# COMM.net
KiCad netlist of a schematic drawn in Altium Designer
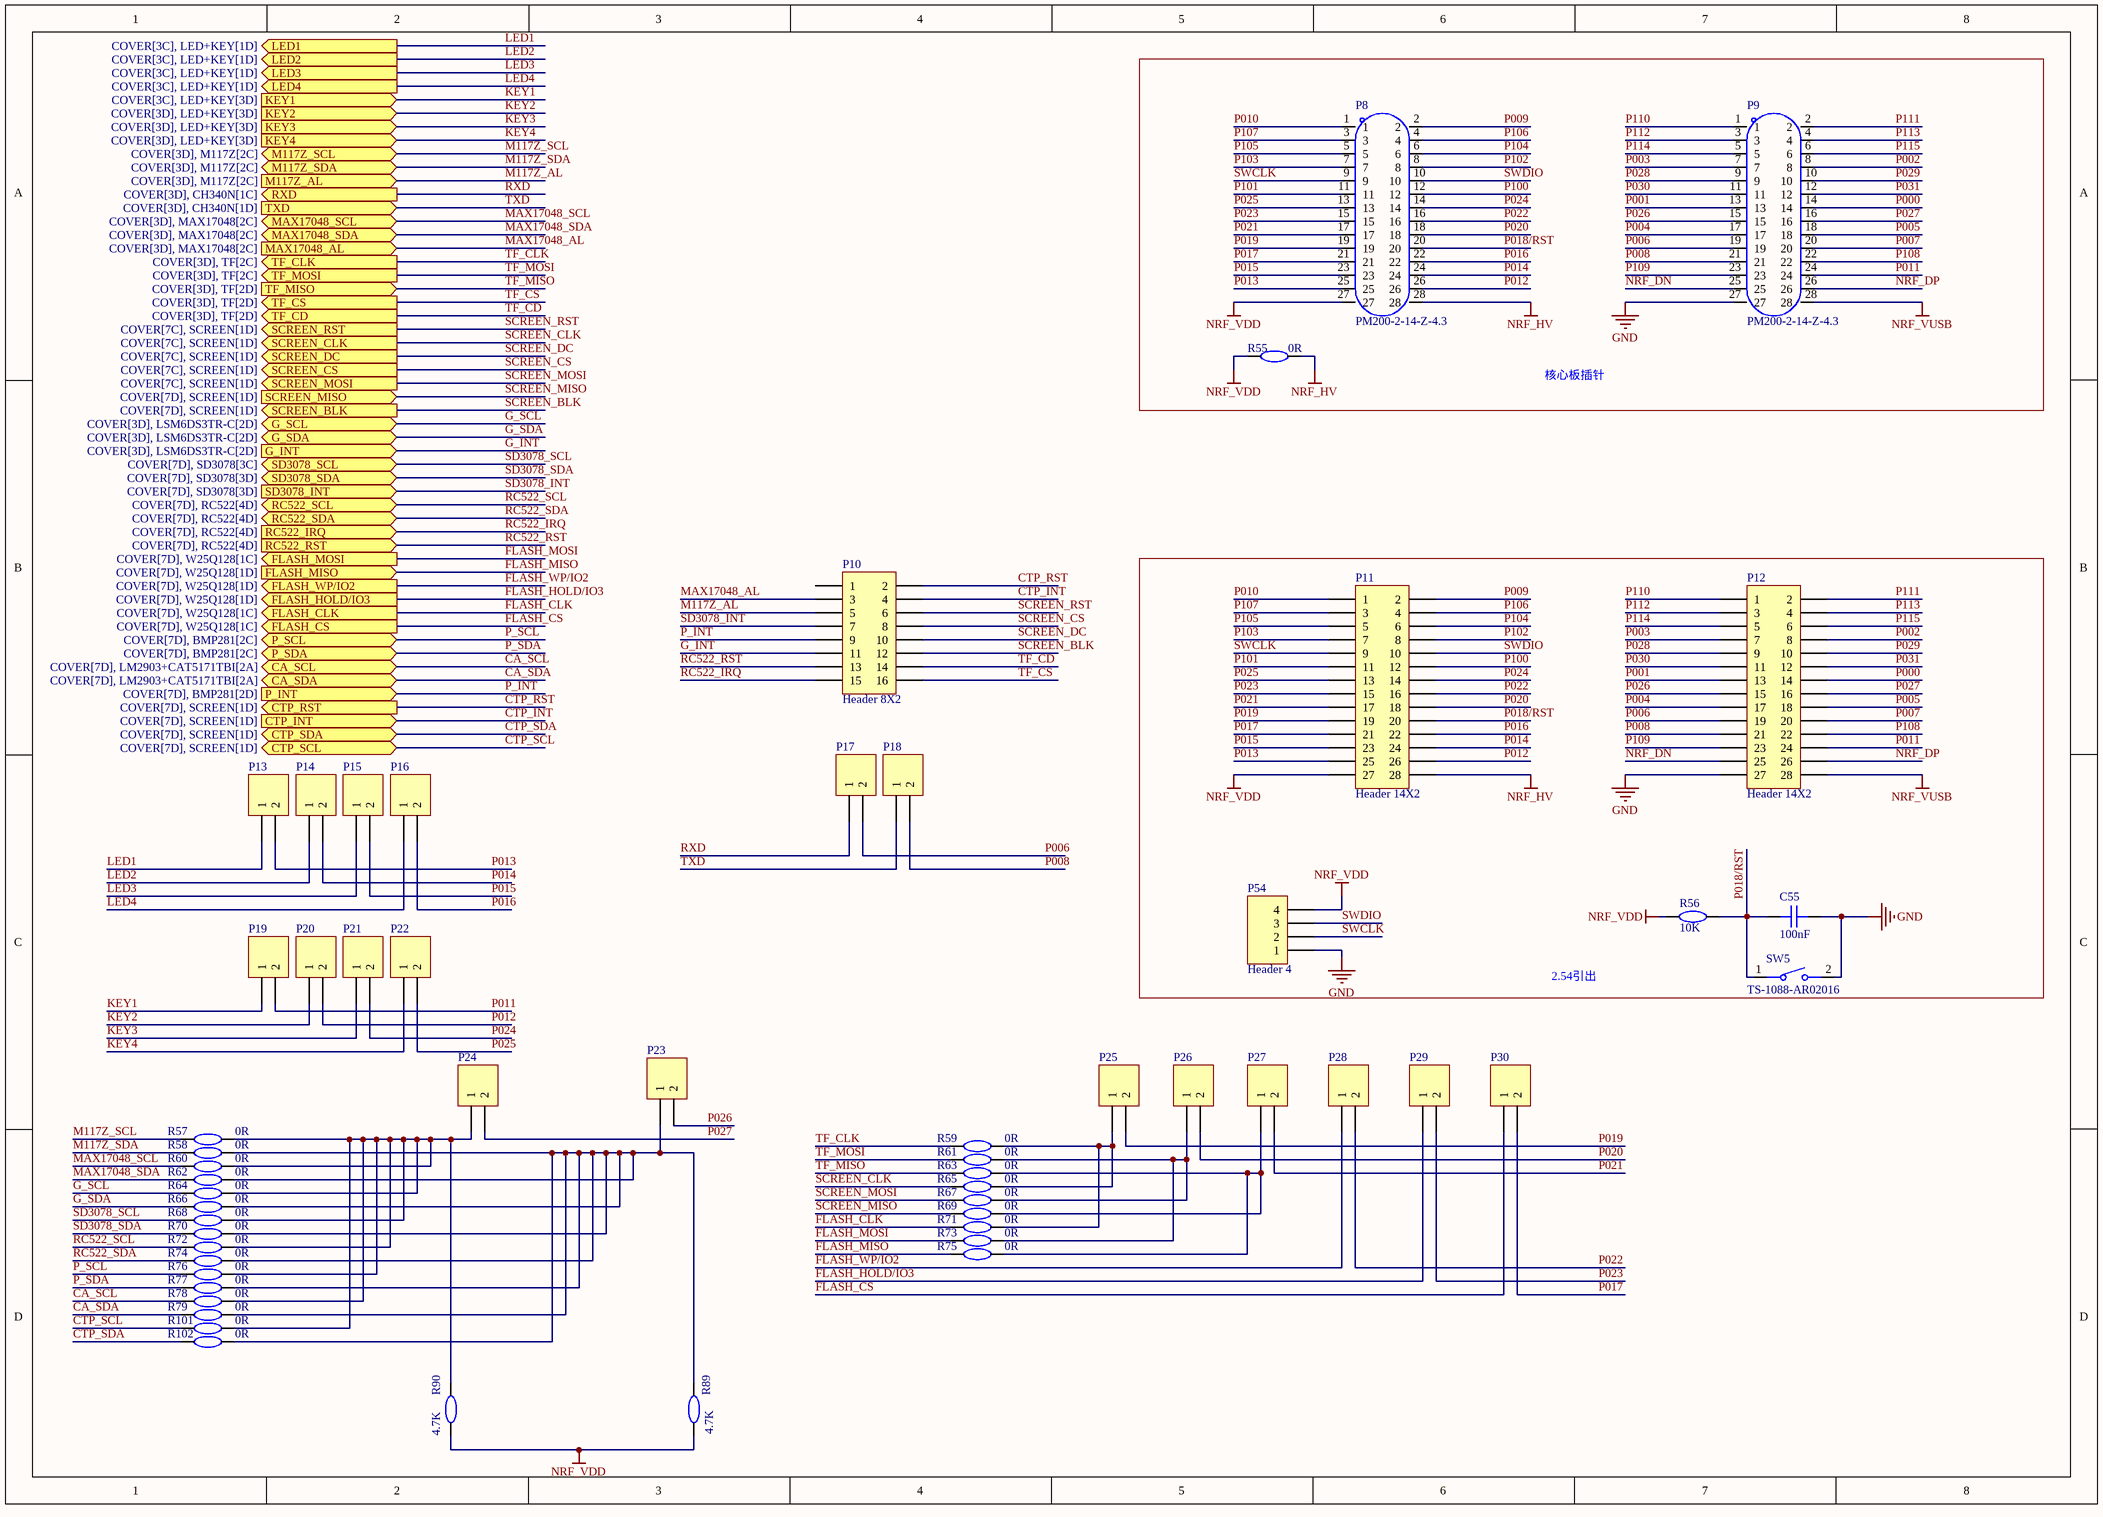
[diagram p0: COMM.SchDoc]

(export (version "E")
  (design (tool "Eeschema 10.0.6"))
  (components
    (comp (ref "C55")
      (value "100nF")
      (footprint "C0402")
      (fields (field (name "NAME") "100nF"))
      (libsource (lib "my_library") (part "CAP_0402"))
    )
    (comp (ref "P8")
      (value "PM200-2-14-Z-4.3")
      (footprint "HDR-TH_28P-P2.00-V-F-R2-C14-S2.00_MF200V-12-28-0590")
      (fields (field (name "MANUFACTURER") "HCTL(华灿天禄)") (field (name "NAME") "PM200-2-14-Z-4.3"))
      (libsource (lib "my_library") (part "PM200-2-14-Z-4.3_C3012178"))
    )
    (comp (ref "P9")
      (value "PM200-2-14-Z-4.3")
      (footprint "HDR-TH_28P-P2.00-V-F-R2-C14-S2.00_MF200V-12-28-0590")
      (fields (field (name "MANUFACTURER") "HCTL(华灿天禄)") (field (name "NAME") "PM200-2-14-Z-4.3"))
      (libsource (lib "my_library") (part "PM200-2-14-Z-4.3_C3012178"))
    )
    (comp (ref "P10")
      (value "Header 8X2")
      (footprint "HDR2X8")
      (description "Header, 8-Pin, Dual row")
      (fields (field (name "PUBLISHER") "Altium Limited"))
      (libsource (lib "Miscellaneous Connectors") (part "Header 8X2"))
    )
    (comp (ref "P11")
      (value "Header 14X2")
      (footprint "HDR2X14")
      (description "Header, 14-Pin, Dual row")
      (fields (field (name "PUBLISHER") "Altium Limited"))
      (libsource (lib "Miscellaneous Connectors") (part "Header 14X2"))
    )
    (comp (ref "P12")
      (value "Header 14X2")
      (footprint "HDR2X14")
      (description "Header, 14-Pin, Dual row")
      (fields (field (name "PUBLISHER") "Altium Limited"))
      (libsource (lib "Miscellaneous Connectors") (part "Header 14X2"))
    )
    (comp (ref "P13")
      (value "Header 2")
      (footprint "HDR1X2")
      (description "Header, 2-Pin")
      (fields (field (name "PUBLISHER") "Altium Limited"))
      (libsource (lib "Miscellaneous Connectors") (part "Header 2"))
    )
    (comp (ref "P14")
      (value "Header 2")
      (footprint "HDR1X2")
      (description "Header, 2-Pin")
      (fields (field (name "PUBLISHER") "Altium Limited"))
      (libsource (lib "Miscellaneous Connectors") (part "Header 2"))
    )
    (comp (ref "P15")
      (value "Header 2")
      (footprint "HDR1X2")
      (description "Header, 2-Pin")
      (fields (field (name "PUBLISHER") "Altium Limited"))
      (libsource (lib "Miscellaneous Connectors") (part "Header 2"))
    )
    (comp (ref "P16")
      (value "Header 2")
      (footprint "HDR1X2")
      (description "Header, 2-Pin")
      (fields (field (name "PUBLISHER") "Altium Limited"))
      (libsource (lib "Miscellaneous Connectors") (part "Header 2"))
    )
    (comp (ref "P17")
      (value "Header 2")
      (footprint "HDR1X2")
      (description "Header, 2-Pin")
      (fields (field (name "PUBLISHER") "Altium Limited"))
      (libsource (lib "Miscellaneous Connectors") (part "Header 2"))
    )
    (comp (ref "P18")
      (value "Header 2")
      (footprint "HDR1X2")
      (description "Header, 2-Pin")
      (fields (field (name "PUBLISHER") "Altium Limited"))
      (libsource (lib "Miscellaneous Connectors") (part "Header 2"))
    )
    (comp (ref "P19")
      (value "Header 2")
      (footprint "HDR1X2")
      (description "Header, 2-Pin")
      (fields (field (name "PUBLISHER") "Altium Limited"))
      (libsource (lib "Miscellaneous Connectors") (part "Header 2"))
    )
    (comp (ref "P20")
      (value "Header 2")
      (footprint "HDR1X2")
      (description "Header, 2-Pin")
      (fields (field (name "PUBLISHER") "Altium Limited"))
      (libsource (lib "Miscellaneous Connectors") (part "Header 2"))
    )
    (comp (ref "P21")
      (value "Header 2")
      (footprint "HDR1X2")
      (description "Header, 2-Pin")
      (fields (field (name "PUBLISHER") "Altium Limited"))
      (libsource (lib "Miscellaneous Connectors") (part "Header 2"))
    )
    (comp (ref "P22")
      (value "Header 2")
      (footprint "HDR1X2")
      (description "Header, 2-Pin")
      (fields (field (name "PUBLISHER") "Altium Limited"))
      (libsource (lib "Miscellaneous Connectors") (part "Header 2"))
    )
    (comp (ref "P23")
      (value "Header 2")
      (footprint "HDR1X2")
      (description "Header, 2-Pin")
      (fields (field (name "PUBLISHER") "Altium Limited"))
      (libsource (lib "Miscellaneous Connectors") (part "Header 2"))
    )
    (comp (ref "P24")
      (value "Header 2")
      (footprint "HDR1X2")
      (description "Header, 2-Pin")
      (fields (field (name "PUBLISHER") "Altium Limited"))
      (libsource (lib "Miscellaneous Connectors") (part "Header 2"))
    )
    (comp (ref "P25")
      (value "Header 2")
      (footprint "HDR1X2")
      (description "Header, 2-Pin")
      (fields (field (name "PUBLISHER") "Altium Limited"))
      (libsource (lib "Miscellaneous Connectors") (part "Header 2"))
    )
    (comp (ref "P26")
      (value "Header 2")
      (footprint "HDR1X2")
      (description "Header, 2-Pin")
      (fields (field (name "PUBLISHER") "Altium Limited"))
      (libsource (lib "Miscellaneous Connectors") (part "Header 2"))
    )
    (comp (ref "P27")
      (value "Header 2")
      (footprint "HDR1X2")
      (description "Header, 2-Pin")
      (fields (field (name "PUBLISHER") "Altium Limited"))
      (libsource (lib "Miscellaneous Connectors") (part "Header 2"))
    )
    (comp (ref "P28")
      (value "Header 2")
      (footprint "HDR1X2")
      (description "Header, 2-Pin")
      (fields (field (name "PUBLISHER") "Altium Limited"))
      (libsource (lib "Miscellaneous Connectors") (part "Header 2"))
    )
    (comp (ref "P29")
      (value "Header 2")
      (footprint "HDR1X2")
      (description "Header, 2-Pin")
      (fields (field (name "PUBLISHER") "Altium Limited"))
      (libsource (lib "Miscellaneous Connectors") (part "Header 2"))
    )
    (comp (ref "P30")
      (value "Header 2")
      (footprint "HDR1X2")
      (description "Header, 2-Pin")
      (fields (field (name "PUBLISHER") "Altium Limited"))
      (libsource (lib "Miscellaneous Connectors") (part "Header 2"))
    )
    (comp (ref "P54")
      (value "Header 4")
      (footprint "HDR1X4")
      (description "Header, 4-Pin")
      (fields (field (name "PUBLISHER") "Altium Limited"))
      (libsource (lib "Miscellaneous Connectors") (part "Header 4"))
    )
    (comp (ref "R55")
      (value "0R")
      (footprint "R0402")
      (fields (field (name "NAME") "0R"))
      (libsource (lib "my_library") (part "Res_0402"))
    )
    (comp (ref "R56")
      (value "10K")
      (footprint "R0402")
      (fields (field (name "NAME") "10K"))
      (libsource (lib "my_library") (part "Res_0402"))
    )
    (comp (ref "R57")
      (value "0R")
      (footprint "R0402")
      (fields (field (name "NAME") "0R"))
      (libsource (lib "my_library") (part "Res_0402"))
    )
    (comp (ref "R58")
      (value "0R")
      (footprint "R0402")
      (fields (field (name "NAME") "0R"))
      (libsource (lib "my_library") (part "Res_0402"))
    )
    (comp (ref "R59")
      (value "0R")
      (footprint "R0402")
      (fields (field (name "NAME") "0R"))
      (libsource (lib "my_library") (part "Res_0402"))
    )
    (comp (ref "R60")
      (value "0R")
      (footprint "R0402")
      (fields (field (name "NAME") "0R"))
      (libsource (lib "my_library") (part "Res_0402"))
    )
    (comp (ref "R61")
      (value "0R")
      (footprint "R0402")
      (fields (field (name "NAME") "0R"))
      (libsource (lib "my_library") (part "Res_0402"))
    )
    (comp (ref "R62")
      (value "0R")
      (footprint "R0402")
      (fields (field (name "NAME") "0R"))
      (libsource (lib "my_library") (part "Res_0402"))
    )
    (comp (ref "R63")
      (value "0R")
      (footprint "R0402")
      (fields (field (name "NAME") "0R"))
      (libsource (lib "my_library") (part "Res_0402"))
    )
    (comp (ref "R64")
      (value "0R")
      (footprint "R0402")
      (fields (field (name "NAME") "0R"))
      (libsource (lib "my_library") (part "Res_0402"))
    )
    (comp (ref "R65")
      (value "0R")
      (footprint "R0402")
      (fields (field (name "NAME") "0R"))
      (libsource (lib "my_library") (part "Res_0402"))
    )
    (comp (ref "R66")
      (value "0R")
      (footprint "R0402")
      (fields (field (name "NAME") "0R"))
      (libsource (lib "my_library") (part "Res_0402"))
    )
    (comp (ref "R67")
      (value "0R")
      (footprint "R0402")
      (fields (field (name "NAME") "0R"))
      (libsource (lib "my_library") (part "Res_0402"))
    )
    (comp (ref "R68")
      (value "0R")
      (footprint "R0402")
      (fields (field (name "NAME") "0R"))
      (libsource (lib "my_library") (part "Res_0402"))
    )
    (comp (ref "R69")
      (value "0R")
      (footprint "R0402")
      (fields (field (name "NAME") "0R"))
      (libsource (lib "my_library") (part "Res_0402"))
    )
    (comp (ref "R70")
      (value "0R")
      (footprint "R0402")
      (fields (field (name "NAME") "0R"))
      (libsource (lib "my_library") (part "Res_0402"))
    )
    (comp (ref "R71")
      (value "0R")
      (footprint "R0402")
      (fields (field (name "NAME") "0R"))
      (libsource (lib "my_library") (part "Res_0402"))
    )
    (comp (ref "R72")
      (value "0R")
      (footprint "R0402")
      (fields (field (name "NAME") "0R"))
      (libsource (lib "my_library") (part "Res_0402"))
    )
    (comp (ref "R73")
      (value "0R")
      (footprint "R0402")
      (fields (field (name "NAME") "0R"))
      (libsource (lib "my_library") (part "Res_0402"))
    )
    (comp (ref "R74")
      (value "0R")
      (footprint "R0402")
      (fields (field (name "NAME") "0R"))
      (libsource (lib "my_library") (part "Res_0402"))
    )
    (comp (ref "R75")
      (value "0R")
      (footprint "R0402")
      (fields (field (name "NAME") "0R"))
      (libsource (lib "my_library") (part "Res_0402"))
    )
    (comp (ref "R76")
      (value "0R")
      (footprint "R0402")
      (fields (field (name "NAME") "0R"))
      (libsource (lib "my_library") (part "Res_0402"))
    )
    (comp (ref "R77")
      (value "0R")
      (footprint "R0402")
      (fields (field (name "NAME") "0R"))
      (libsource (lib "my_library") (part "Res_0402"))
    )
    (comp (ref "R78")
      (value "0R")
      (footprint "R0402")
      (fields (field (name "NAME") "0R"))
      (libsource (lib "my_library") (part "Res_0402"))
    )
    (comp (ref "R79")
      (value "0R")
      (footprint "R0402")
      (fields (field (name "NAME") "0R"))
      (libsource (lib "my_library") (part "Res_0402"))
    )
    (comp (ref "R89")
      (value "4.7K")
      (footprint "R0402")
      (fields (field (name "NAME") "4.7K"))
      (libsource (lib "my_library") (part "Res_0402"))
    )
    (comp (ref "R90")
      (value "4.7K")
      (footprint "R0402")
      (fields (field (name "NAME") "4.7K"))
      (libsource (lib "my_library") (part "Res_0402"))
    )
    (comp (ref "R101")
      (value "0R")
      (footprint "R0402")
      (fields (field (name "NAME") "0R"))
      (libsource (lib "my_library") (part "Res_0402"))
    )
    (comp (ref "R102")
      (value "0R")
      (footprint "R0402")
      (fields (field (name "NAME") "0R"))
      (libsource (lib "my_library") (part "Res_0402"))
    )
    (comp (ref "SW5")
      (value "TS-1088-AR02016")
      (footprint "SW-SMD_L3.9-W3.0-P4.45")
      (fields (field (name "MANUFACTURER") "XUNPU(讯普)") (field (name "NAME") "TS-1088-AR02016"))
      (libsource (lib "my_library") (part "TS-1088-AR02016"))
    )
  )
  (nets
    (net (code "1") (name "/CA_SCL") (class "Default")
      (node (ref "R78") (pin "1") (pinfunction "1_1") (pintype "passive"))
    )
    (net (code "2") (name "/CA_SDA") (class "Default")
      (node (ref "R79") (pin "1") (pinfunction "1_1") (pintype "passive"))
    )
    (net (code "3") (name "/CTP_INT") (class "Default")
      (node (ref "P10") (pin "4") (pinfunction "4_4") (pintype "passive"))
    )
    (net (code "4") (name "/CTP_RST") (class "Default")
      (node (ref "P10") (pin "2") (pinfunction "2_2") (pintype "passive"))
    )
    (net (code "5") (name "/CTP_SCL") (class "Default")
      (node (ref "R101") (pin "1") (pinfunction "1_1") (pintype "passive"))
    )
    (net (code "6") (name "/CTP_SDA") (class "Default")
      (node (ref "R102") (pin "1") (pinfunction "1_1") (pintype "passive"))
    )
    (net (code "7") (name "/FLASH_CLK") (class "Default")
      (node (ref "R71") (pin "1") (pinfunction "1_1") (pintype "passive"))
    )
    (net (code "8") (name "/FLASH_CS") (class "Default")
      (node (ref "P30") (pin "1") (pinfunction "1_1") (pintype "passive"))
    )
    (net (code "9") (name "/FLASH_HOLD{slash}IO3") (class "Default")
      (node (ref "P29") (pin "1") (pinfunction "1_1") (pintype "passive"))
    )
    (net (code "10") (name "/FLASH_MISO") (class "Default")
      (node (ref "R75") (pin "1") (pinfunction "1_1") (pintype "passive"))
    )
    (net (code "11") (name "/FLASH_MOSI") (class "Default")
      (node (ref "R73") (pin "1") (pinfunction "1_1") (pintype "passive"))
    )
    (net (code "12") (name "/FLASH_WP{slash}IO2") (class "Default")
      (node (ref "P28") (pin "1") (pinfunction "1_1") (pintype "passive"))
    )
    (net (code "13") (name "/G_INT") (class "Default")
      (node (ref "P10") (pin "11") (pinfunction "11_11") (pintype "passive"))
    )
    (net (code "14") (name "/G_SCL") (class "Default")
      (node (ref "R64") (pin "1") (pinfunction "1_1") (pintype "passive"))
    )
    (net (code "15") (name "/G_SDA") (class "Default")
      (node (ref "R66") (pin "1") (pinfunction "1_1") (pintype "passive"))
    )
    (net (code "16") (name "/KEY1") (class "Default")
      (node (ref "P19") (pin "1") (pinfunction "1_1") (pintype "passive"))
    )
    (net (code "17") (name "/KEY2") (class "Default")
      (node (ref "P20") (pin "1") (pinfunction "1_1") (pintype "passive"))
    )
    (net (code "18") (name "/KEY3") (class "Default")
      (node (ref "P21") (pin "1") (pinfunction "1_1") (pintype "passive"))
    )
    (net (code "19") (name "/KEY4") (class "Default")
      (node (ref "P22") (pin "1") (pinfunction "1_1") (pintype "passive"))
    )
    (net (code "20") (name "/LED1") (class "Default")
      (node (ref "P13") (pin "1") (pinfunction "1_1") (pintype "passive"))
    )
    (net (code "21") (name "/LED2") (class "Default")
      (node (ref "P14") (pin "1") (pinfunction "1_1") (pintype "passive"))
    )
    (net (code "22") (name "/LED3") (class "Default")
      (node (ref "P15") (pin "1") (pinfunction "1_1") (pintype "passive"))
    )
    (net (code "23") (name "/LED4") (class "Default")
      (node (ref "P16") (pin "1") (pinfunction "1_1") (pintype "passive"))
    )
    (net (code "24") (name "/M117Z_AL") (class "Default")
      (node (ref "P10") (pin "5") (pinfunction "5_5") (pintype "passive"))
    )
    (net (code "25") (name "/M117Z_SCL") (class "Default")
      (node (ref "R57") (pin "1") (pinfunction "1_1") (pintype "passive"))
    )
    (net (code "26") (name "/M117Z_SDA") (class "Default")
      (node (ref "R58") (pin "1") (pinfunction "1_1") (pintype "passive"))
    )
    (net (code "27") (name "/MAX17048_AL") (class "Default")
      (node (ref "P10") (pin "3") (pinfunction "3_3") (pintype "passive"))
    )
    (net (code "28") (name "/MAX17048_SCL") (class "Default")
      (node (ref "R60") (pin "1") (pinfunction "1_1") (pintype "passive"))
    )
    (net (code "29") (name "/MAX17048_SDA") (class "Default")
      (node (ref "R62") (pin "1") (pinfunction "1_1") (pintype "passive"))
    )
    (net (code "30") (name "/NRF_DN") (class "Default")
      (node (ref "P12") (pin "25") (pinfunction "25_25") (pintype "passive"))
      (node (ref "P9") (pin "25") (pinfunction "25_25") (pintype "passive"))
    )
    (net (code "31") (name "/NRF_DP") (class "Default")
      (node (ref "P12") (pin "26") (pinfunction "26_26") (pintype "passive"))
      (node (ref "P9") (pin "26") (pinfunction "26_26") (pintype "passive"))
    )
    (net (code "32") (name "/P000") (class "Default")
      (node (ref "P12") (pin "14") (pinfunction "14_14") (pintype "passive"))
      (node (ref "P9") (pin "14") (pinfunction "14_14") (pintype "passive"))
    )
    (net (code "33") (name "/P001") (class "Default")
      (node (ref "P12") (pin "13") (pinfunction "13_13") (pintype "passive"))
      (node (ref "P9") (pin "13") (pinfunction "13_13") (pintype "passive"))
    )
    (net (code "34") (name "/P002") (class "Default")
      (node (ref "P12") (pin "8") (pinfunction "8_8") (pintype "passive"))
      (node (ref "P9") (pin "8") (pinfunction "8_8") (pintype "passive"))
    )
    (net (code "35") (name "/P003") (class "Default")
      (node (ref "P12") (pin "7") (pinfunction "7_7") (pintype "passive"))
      (node (ref "P9") (pin "7") (pinfunction "7_7") (pintype "passive"))
    )
    (net (code "36") (name "/P004") (class "Default")
      (node (ref "P12") (pin "17") (pinfunction "17_17") (pintype "passive"))
      (node (ref "P9") (pin "17") (pinfunction "17_17") (pintype "passive"))
    )
    (net (code "37") (name "/P005") (class "Default")
      (node (ref "P12") (pin "18") (pinfunction "18_18") (pintype "passive"))
      (node (ref "P9") (pin "18") (pinfunction "18_18") (pintype "passive"))
    )
    (net (code "38") (name "/P006") (class "Default")
      (node (ref "P12") (pin "19") (pinfunction "19_19") (pintype "passive"))
      (node (ref "P17") (pin "2") (pinfunction "2_2") (pintype "passive"))
      (node (ref "P9") (pin "19") (pinfunction "19_19") (pintype "passive"))
    )
    (net (code "39") (name "/P007") (class "Default")
      (node (ref "P12") (pin "20") (pinfunction "20_20") (pintype "passive"))
      (node (ref "P9") (pin "20") (pinfunction "20_20") (pintype "passive"))
    )
    (net (code "40") (name "/P008") (class "Default")
      (node (ref "P12") (pin "21") (pinfunction "21_21") (pintype "passive"))
      (node (ref "P18") (pin "2") (pinfunction "2_2") (pintype "passive"))
      (node (ref "P9") (pin "21") (pinfunction "21_21") (pintype "passive"))
    )
    (net (code "41") (name "/P009") (class "Default")
      (node (ref "P11") (pin "2") (pinfunction "2_2") (pintype "passive"))
      (node (ref "P8") (pin "2") (pinfunction "2_2") (pintype "passive"))
    )
    (net (code "42") (name "/P010") (class "Default")
      (node (ref "P11") (pin "1") (pinfunction "1_1") (pintype "passive"))
      (node (ref "P8") (pin "1") (pinfunction "1_1") (pintype "passive"))
    )
    (net (code "43") (name "/P011") (class "Default")
      (node (ref "P12") (pin "24") (pinfunction "24_24") (pintype "passive"))
      (node (ref "P19") (pin "2") (pinfunction "2_2") (pintype "passive"))
      (node (ref "P9") (pin "24") (pinfunction "24_24") (pintype "passive"))
    )
    (net (code "44") (name "/P012") (class "Default")
      (node (ref "P11") (pin "26") (pinfunction "26_26") (pintype "passive"))
      (node (ref "P20") (pin "2") (pinfunction "2_2") (pintype "passive"))
      (node (ref "P8") (pin "26") (pinfunction "26_26") (pintype "passive"))
    )
    (net (code "45") (name "/P013") (class "Default")
      (node (ref "P11") (pin "25") (pinfunction "25_25") (pintype "passive"))
      (node (ref "P13") (pin "2") (pinfunction "2_2") (pintype "passive"))
      (node (ref "P8") (pin "25") (pinfunction "25_25") (pintype "passive"))
    )
    (net (code "46") (name "/P014") (class "Default")
      (node (ref "P11") (pin "24") (pinfunction "24_24") (pintype "passive"))
      (node (ref "P14") (pin "2") (pinfunction "2_2") (pintype "passive"))
      (node (ref "P8") (pin "24") (pinfunction "24_24") (pintype "passive"))
    )
    (net (code "47") (name "/P015") (class "Default")
      (node (ref "P11") (pin "23") (pinfunction "23_23") (pintype "passive"))
      (node (ref "P15") (pin "2") (pinfunction "2_2") (pintype "passive"))
      (node (ref "P8") (pin "23") (pinfunction "23_23") (pintype "passive"))
    )
    (net (code "48") (name "/P016") (class "Default")
      (node (ref "P11") (pin "22") (pinfunction "22_22") (pintype "passive"))
      (node (ref "P16") (pin "2") (pinfunction "2_2") (pintype "passive"))
      (node (ref "P8") (pin "22") (pinfunction "22_22") (pintype "passive"))
    )
    (net (code "49") (name "/P017") (class "Default")
      (node (ref "P11") (pin "21") (pinfunction "21_21") (pintype "passive"))
      (node (ref "P30") (pin "2") (pinfunction "2_2") (pintype "passive"))
      (node (ref "P8") (pin "21") (pinfunction "21_21") (pintype "passive"))
    )
    (net (code "50") (name "/P018{slash}RST") (class "Default")
      (node (ref "C55") (pin "1") (pinfunction "1_1") (pintype "passive"))
      (node (ref "P11") (pin "20") (pinfunction "20_20") (pintype "passive"))
      (node (ref "P8") (pin "20") (pinfunction "20_20") (pintype "passive"))
      (node (ref "R56") (pin "2") (pinfunction "2_2") (pintype "passive"))
      (node (ref "SW5") (pin "1") (pinfunction "1_1") (pintype "passive"))
    )
    (net (code "51") (name "/P019") (class "Default")
      (node (ref "P11") (pin "19") (pinfunction "19_19") (pintype "passive"))
      (node (ref "P25") (pin "2") (pinfunction "2_2") (pintype "passive"))
      (node (ref "P8") (pin "19") (pinfunction "19_19") (pintype "passive"))
    )
    (net (code "52") (name "/P020") (class "Default")
      (node (ref "P11") (pin "18") (pinfunction "18_18") (pintype "passive"))
      (node (ref "P26") (pin "2") (pinfunction "2_2") (pintype "passive"))
      (node (ref "P8") (pin "18") (pinfunction "18_18") (pintype "passive"))
    )
    (net (code "53") (name "/P021") (class "Default")
      (node (ref "P11") (pin "17") (pinfunction "17_17") (pintype "passive"))
      (node (ref "P27") (pin "2") (pinfunction "2_2") (pintype "passive"))
      (node (ref "P8") (pin "17") (pinfunction "17_17") (pintype "passive"))
    )
    (net (code "54") (name "/P022") (class "Default")
      (node (ref "P11") (pin "16") (pinfunction "16_16") (pintype "passive"))
      (node (ref "P28") (pin "2") (pinfunction "2_2") (pintype "passive"))
      (node (ref "P8") (pin "16") (pinfunction "16_16") (pintype "passive"))
    )
    (net (code "55") (name "/P023") (class "Default")
      (node (ref "P11") (pin "15") (pinfunction "15_15") (pintype "passive"))
      (node (ref "P29") (pin "2") (pinfunction "2_2") (pintype "passive"))
      (node (ref "P8") (pin "15") (pinfunction "15_15") (pintype "passive"))
    )
    (net (code "56") (name "/P024") (class "Default")
      (node (ref "P11") (pin "14") (pinfunction "14_14") (pintype "passive"))
      (node (ref "P21") (pin "2") (pinfunction "2_2") (pintype "passive"))
      (node (ref "P8") (pin "14") (pinfunction "14_14") (pintype "passive"))
    )
    (net (code "57") (name "/P025") (class "Default")
      (node (ref "P11") (pin "13") (pinfunction "13_13") (pintype "passive"))
      (node (ref "P22") (pin "2") (pinfunction "2_2") (pintype "passive"))
      (node (ref "P8") (pin "13") (pinfunction "13_13") (pintype "passive"))
    )
    (net (code "58") (name "/P026") (class "Default")
      (node (ref "P12") (pin "15") (pinfunction "15_15") (pintype "passive"))
      (node (ref "P23") (pin "2") (pinfunction "2_2") (pintype "passive"))
      (node (ref "P9") (pin "15") (pinfunction "15_15") (pintype "passive"))
    )
    (net (code "59") (name "/P027") (class "Default")
      (node (ref "P12") (pin "16") (pinfunction "16_16") (pintype "passive"))
      (node (ref "P24") (pin "2") (pinfunction "2_2") (pintype "passive"))
      (node (ref "P9") (pin "16") (pinfunction "16_16") (pintype "passive"))
    )
    (net (code "60") (name "/P028") (class "Default")
      (node (ref "P12") (pin "9") (pinfunction "9_9") (pintype "passive"))
      (node (ref "P9") (pin "9") (pinfunction "9_9") (pintype "passive"))
    )
    (net (code "61") (name "/P029") (class "Default")
      (node (ref "P12") (pin "10") (pinfunction "10_10") (pintype "passive"))
      (node (ref "P9") (pin "10") (pinfunction "10_10") (pintype "passive"))
    )
    (net (code "62") (name "/P030") (class "Default")
      (node (ref "P12") (pin "11") (pinfunction "11_11") (pintype "passive"))
      (node (ref "P9") (pin "11") (pinfunction "11_11") (pintype "passive"))
    )
    (net (code "63") (name "/P031") (class "Default")
      (node (ref "P12") (pin "12") (pinfunction "12_12") (pintype "passive"))
      (node (ref "P9") (pin "12") (pinfunction "12_12") (pintype "passive"))
    )
    (net (code "64") (name "/P100") (class "Default")
      (node (ref "P11") (pin "12") (pinfunction "12_12") (pintype "passive"))
      (node (ref "P8") (pin "12") (pinfunction "12_12") (pintype "passive"))
    )
    (net (code "65") (name "/P101") (class "Default")
      (node (ref "P11") (pin "11") (pinfunction "11_11") (pintype "passive"))
      (node (ref "P8") (pin "11") (pinfunction "11_11") (pintype "passive"))
    )
    (net (code "66") (name "/P102") (class "Default")
      (node (ref "P11") (pin "8") (pinfunction "8_8") (pintype "passive"))
      (node (ref "P8") (pin "8") (pinfunction "8_8") (pintype "passive"))
    )
    (net (code "67") (name "/P103") (class "Default")
      (node (ref "P11") (pin "7") (pinfunction "7_7") (pintype "passive"))
      (node (ref "P8") (pin "7") (pinfunction "7_7") (pintype "passive"))
    )
    (net (code "68") (name "/P104") (class "Default")
      (node (ref "P11") (pin "6") (pinfunction "6_6") (pintype "passive"))
      (node (ref "P8") (pin "6") (pinfunction "6_6") (pintype "passive"))
    )
    (net (code "69") (name "/P105") (class "Default")
      (node (ref "P11") (pin "5") (pinfunction "5_5") (pintype "passive"))
      (node (ref "P8") (pin "5") (pinfunction "5_5") (pintype "passive"))
    )
    (net (code "70") (name "/P106") (class "Default")
      (node (ref "P11") (pin "4") (pinfunction "4_4") (pintype "passive"))
      (node (ref "P8") (pin "4") (pinfunction "4_4") (pintype "passive"))
    )
    (net (code "71") (name "/P107") (class "Default")
      (node (ref "P11") (pin "3") (pinfunction "3_3") (pintype "passive"))
      (node (ref "P8") (pin "3") (pinfunction "3_3") (pintype "passive"))
    )
    (net (code "72") (name "/P108") (class "Default")
      (node (ref "P12") (pin "22") (pinfunction "22_22") (pintype "passive"))
      (node (ref "P9") (pin "22") (pinfunction "22_22") (pintype "passive"))
    )
    (net (code "73") (name "/P109") (class "Default")
      (node (ref "P12") (pin "23") (pinfunction "23_23") (pintype "passive"))
      (node (ref "P9") (pin "23") (pinfunction "23_23") (pintype "passive"))
    )
    (net (code "74") (name "/P110") (class "Default")
      (node (ref "P12") (pin "1") (pinfunction "1_1") (pintype "passive"))
      (node (ref "P9") (pin "1") (pinfunction "1_1") (pintype "passive"))
    )
    (net (code "75") (name "/P111") (class "Default")
      (node (ref "P12") (pin "2") (pinfunction "2_2") (pintype "passive"))
      (node (ref "P9") (pin "2") (pinfunction "2_2") (pintype "passive"))
    )
    (net (code "76") (name "/P112") (class "Default")
      (node (ref "P12") (pin "3") (pinfunction "3_3") (pintype "passive"))
      (node (ref "P9") (pin "3") (pinfunction "3_3") (pintype "passive"))
    )
    (net (code "77") (name "/P113") (class "Default")
      (node (ref "P12") (pin "4") (pinfunction "4_4") (pintype "passive"))
      (node (ref "P9") (pin "4") (pinfunction "4_4") (pintype "passive"))
    )
    (net (code "78") (name "/P114") (class "Default")
      (node (ref "P12") (pin "5") (pinfunction "5_5") (pintype "passive"))
      (node (ref "P9") (pin "5") (pinfunction "5_5") (pintype "passive"))
    )
    (net (code "79") (name "/P115") (class "Default")
      (node (ref "P12") (pin "6") (pinfunction "6_6") (pintype "passive"))
      (node (ref "P9") (pin "6") (pinfunction "6_6") (pintype "passive"))
    )
    (net (code "80") (name "/P_INT") (class "Default")
      (node (ref "P10") (pin "9") (pinfunction "9_9") (pintype "passive"))
    )
    (net (code "81") (name "/P_SCL") (class "Default")
      (node (ref "R76") (pin "1") (pinfunction "1_1") (pintype "passive"))
    )
    (net (code "82") (name "/P_SDA") (class "Default")
      (node (ref "R77") (pin "1") (pinfunction "1_1") (pintype "passive"))
    )
    (net (code "83") (name "/RC522_IRQ") (class "Default")
      (node (ref "P10") (pin "15") (pinfunction "15_15") (pintype "passive"))
    )
    (net (code "84") (name "/RC522_RST") (class "Default")
      (node (ref "P10") (pin "13") (pinfunction "13_13") (pintype "passive"))
    )
    (net (code "85") (name "/RC522_SCL") (class "Default")
      (node (ref "R72") (pin "1") (pinfunction "1_1") (pintype "passive"))
    )
    (net (code "86") (name "/RC522_SDA") (class "Default")
      (node (ref "R74") (pin "1") (pinfunction "1_1") (pintype "passive"))
    )
    (net (code "87") (name "/RXD") (class "Default")
      (node (ref "P17") (pin "1") (pinfunction "1_1") (pintype "passive"))
    )
    (net (code "88") (name "/SCREEN_BLK") (class "Default")
      (node (ref "P10") (pin "12") (pinfunction "12_12") (pintype "passive"))
    )
    (net (code "89") (name "/SCREEN_CLK") (class "Default")
      (node (ref "R65") (pin "1") (pinfunction "1_1") (pintype "passive"))
    )
    (net (code "90") (name "/SCREEN_CS") (class "Default")
      (node (ref "P10") (pin "8") (pinfunction "8_8") (pintype "passive"))
    )
    (net (code "91") (name "/SCREEN_DC") (class "Default")
      (node (ref "P10") (pin "10") (pinfunction "10_10") (pintype "passive"))
    )
    (net (code "92") (name "/SCREEN_MISO") (class "Default")
      (node (ref "R69") (pin "1") (pinfunction "1_1") (pintype "passive"))
    )
    (net (code "93") (name "/SCREEN_MOSI") (class "Default")
      (node (ref "R67") (pin "1") (pinfunction "1_1") (pintype "passive"))
    )
    (net (code "94") (name "/SCREEN_RST") (class "Default")
      (node (ref "P10") (pin "6") (pinfunction "6_6") (pintype "passive"))
    )
    (net (code "95") (name "/SD3078_INT") (class "Default")
      (node (ref "P10") (pin "7") (pinfunction "7_7") (pintype "passive"))
    )
    (net (code "96") (name "/SD3078_SCL") (class "Default")
      (node (ref "R68") (pin "1") (pinfunction "1_1") (pintype "passive"))
    )
    (net (code "97") (name "/SD3078_SDA") (class "Default")
      (node (ref "R70") (pin "1") (pinfunction "1_1") (pintype "passive"))
    )
    (net (code "98") (name "/SWCLK") (class "Default")
      (node (ref "P11") (pin "9") (pinfunction "9_9") (pintype "passive"))
      (node (ref "P54") (pin "2") (pinfunction "2_2") (pintype "passive"))
      (node (ref "P8") (pin "9") (pinfunction "9_9") (pintype "passive"))
    )
    (net (code "99") (name "/SWDIO") (class "Default")
      (node (ref "P11") (pin "10") (pinfunction "10_10") (pintype "passive"))
      (node (ref "P54") (pin "3") (pinfunction "3_3") (pintype "passive"))
      (node (ref "P8") (pin "10") (pinfunction "10_10") (pintype "passive"))
    )
    (net (code "100") (name "/TF_CD") (class "Default")
      (node (ref "P10") (pin "14") (pinfunction "14_14") (pintype "passive"))
    )
    (net (code "101") (name "/TF_CLK") (class "Default")
      (node (ref "R59") (pin "1") (pinfunction "1_1") (pintype "passive"))
    )
    (net (code "102") (name "/TF_CS") (class "Default")
      (node (ref "P10") (pin "16") (pinfunction "16_16") (pintype "passive"))
    )
    (net (code "103") (name "/TF_MISO") (class "Default")
      (node (ref "R63") (pin "1") (pinfunction "1_1") (pintype "passive"))
    )
    (net (code "104") (name "/TF_MOSI") (class "Default")
      (node (ref "R61") (pin "1") (pinfunction "1_1") (pintype "passive"))
    )
    (net (code "105") (name "/TXD") (class "Default")
      (node (ref "P18") (pin "1") (pinfunction "1_1") (pintype "passive"))
    )
    (net (code "106") (name "GND") (class "Default")
      (node (ref "C55") (pin "2") (pinfunction "2_2") (pintype "passive"))
      (node (ref "P12") (pin "27") (pinfunction "27_27") (pintype "passive"))
      (node (ref "P54") (pin "1") (pinfunction "1_1") (pintype "passive"))
      (node (ref "P9") (pin "27") (pinfunction "27_27") (pintype "passive"))
      (node (ref "SW5") (pin "2") (pinfunction "2_2") (pintype "passive"))
    )
    (net (code "107") (name "NRF_HV") (class "Default")
      (node (ref "P11") (pin "28") (pinfunction "28_28") (pintype "passive"))
      (node (ref "P8") (pin "28") (pinfunction "28_28") (pintype "passive"))
      (node (ref "R55") (pin "2") (pinfunction "2_2") (pintype "passive"))
    )
    (net (code "108") (name "NRF_VDD") (class "Default")
      (node (ref "P11") (pin "27") (pinfunction "27_27") (pintype "passive"))
      (node (ref "P54") (pin "4") (pinfunction "4_4") (pintype "passive"))
      (node (ref "P8") (pin "27") (pinfunction "27_27") (pintype "passive"))
      (node (ref "R55") (pin "1") (pinfunction "1_1") (pintype "passive"))
      (node (ref "R56") (pin "1") (pinfunction "1_1") (pintype "passive"))
      (node (ref "R89") (pin "1") (pinfunction "1_1") (pintype "passive"))
      (node (ref "R90") (pin "1") (pinfunction "1_1") (pintype "passive"))
    )
    (net (code "109") (name "NRF_VUSB") (class "Default")
      (node (ref "P12") (pin "28") (pinfunction "28_28") (pintype "passive"))
      (node (ref "P9") (pin "28") (pinfunction "28_28") (pintype "passive"))
    )
    (net (code "110") (name "Net-(P23-Pad1)") (class "Default")
      (node (ref "P23") (pin "1") (pinfunction "1_1") (pintype "passive"))
      (node (ref "R102") (pin "2") (pinfunction "2_2") (pintype "passive"))
      (node (ref "R58") (pin "2") (pinfunction "2_2") (pintype "passive"))
      (node (ref "R62") (pin "2") (pinfunction "2_2") (pintype "passive"))
      (node (ref "R66") (pin "2") (pinfunction "2_2") (pintype "passive"))
      (node (ref "R70") (pin "2") (pinfunction "2_2") (pintype "passive"))
      (node (ref "R74") (pin "2") (pinfunction "2_2") (pintype "passive"))
      (node (ref "R77") (pin "2") (pinfunction "2_2") (pintype "passive"))
      (node (ref "R79") (pin "2") (pinfunction "2_2") (pintype "passive"))
      (node (ref "R89") (pin "2") (pinfunction "2_2") (pintype "passive"))
    )
    (net (code "111") (name "Net-(P24-Pad1)") (class "Default")
      (node (ref "P24") (pin "1") (pinfunction "1_1") (pintype "passive"))
      (node (ref "R101") (pin "2") (pinfunction "2_2") (pintype "passive"))
      (node (ref "R57") (pin "2") (pinfunction "2_2") (pintype "passive"))
      (node (ref "R60") (pin "2") (pinfunction "2_2") (pintype "passive"))
      (node (ref "R64") (pin "2") (pinfunction "2_2") (pintype "passive"))
      (node (ref "R68") (pin "2") (pinfunction "2_2") (pintype "passive"))
      (node (ref "R72") (pin "2") (pinfunction "2_2") (pintype "passive"))
      (node (ref "R76") (pin "2") (pinfunction "2_2") (pintype "passive"))
      (node (ref "R78") (pin "2") (pinfunction "2_2") (pintype "passive"))
      (node (ref "R90") (pin "2") (pinfunction "2_2") (pintype "passive"))
    )
    (net (code "112") (name "Net-(P25-Pad1)") (class "Default")
      (node (ref "P25") (pin "1") (pinfunction "1_1") (pintype "passive"))
      (node (ref "R59") (pin "2") (pinfunction "2_2") (pintype "passive"))
      (node (ref "R65") (pin "2") (pinfunction "2_2") (pintype "passive"))
      (node (ref "R71") (pin "2") (pinfunction "2_2") (pintype "passive"))
    )
    (net (code "113") (name "Net-(P26-Pad1)") (class "Default")
      (node (ref "P26") (pin "1") (pinfunction "1_1") (pintype "passive"))
      (node (ref "R61") (pin "2") (pinfunction "2_2") (pintype "passive"))
      (node (ref "R67") (pin "2") (pinfunction "2_2") (pintype "passive"))
      (node (ref "R73") (pin "2") (pinfunction "2_2") (pintype "passive"))
    )
    (net (code "114") (name "Net-(P27-Pad1)") (class "Default")
      (node (ref "P27") (pin "1") (pinfunction "1_1") (pintype "passive"))
      (node (ref "R63") (pin "2") (pinfunction "2_2") (pintype "passive"))
      (node (ref "R69") (pin "2") (pinfunction "2_2") (pintype "passive"))
      (node (ref "R75") (pin "2") (pinfunction "2_2") (pintype "passive"))
    )
    (net (code "115") (name "unconnected-(P10-Pad1)") (class "Default")
      (node (ref "P10") (pin "1") (pinfunction "1_1") (pintype "passive"))
    )
  )
)
